# LEDCON_PCB.net
KiCad netlist of a schematic drawn in EAGLE
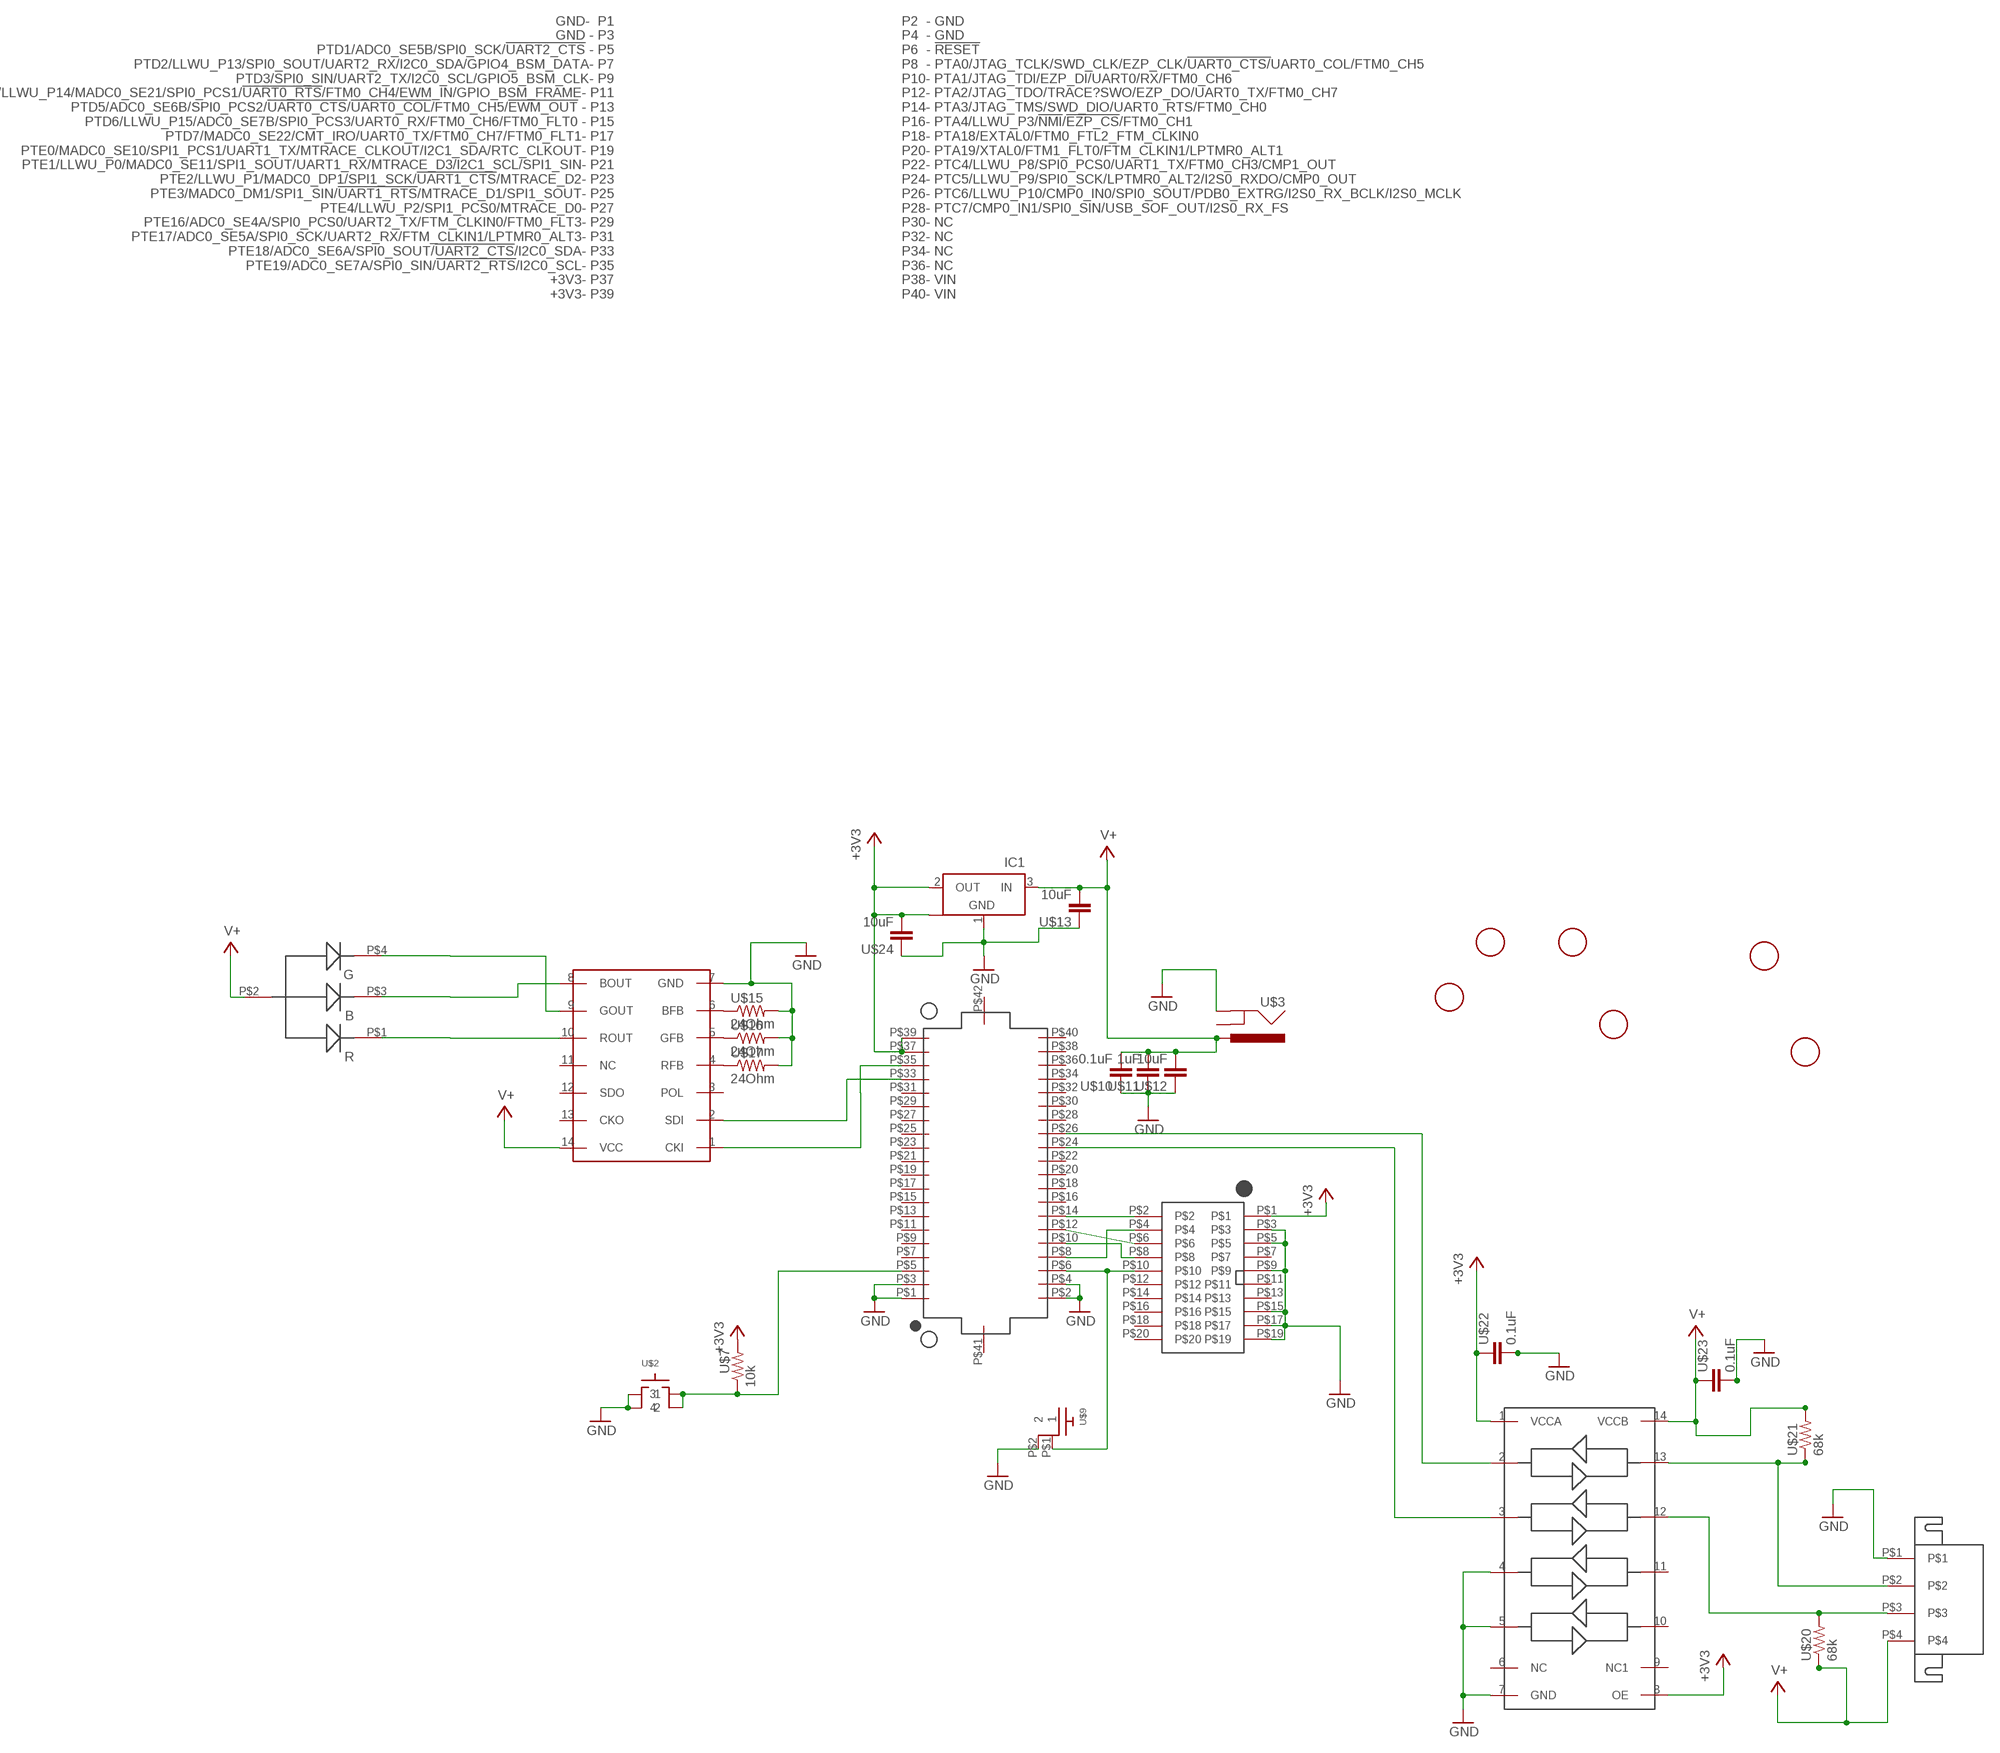
[diagram p0: schematic, sheet 1]

(export (version "E")
  (design (tool "Eeschema 10.0.6"))
  (components
    (comp (ref "IC1")
      (value "NCP1117ST33T3G_1")
      (footprint "eagle-import:SOT223")
      (fields (field (name "MFGN") "OnSemi") (field (name "MFGP") "NCP1117ST33T3G"))
      (libsource (lib "eagle-import") (part "NCP1117ST33T3G_1"))
    )
    (comp (ref "U$1")
      (value "MATE-N-LOK_643230-1")
      (footprint "eagle-import:MATE-N-LOK_643230-1")
      (fields (field (name "MFGN") "TE Connectivity") (field (name "MFGP") "643230-1"))
      (libsource (lib "eagle-import") (part "MATE-N-LOK_643230-1"))
    )
    (comp (ref "U$2")
      (value "SWITCH-TACTILE")
      (footprint "eagle-import:ESWITCH-TL3301PF")
      (libsource (lib "eagle-import") (part "SWITCH-TACTILE"))
    )
    (comp (ref "U$3")
      (value "BARREL_CUI_PJ-002A")
      (footprint "eagle-import:BARREL_CUI_PJ-002A")
      (libsource (lib "eagle-import") (part "BARREL_CUI_PJ-002A"))
    )
    (comp (ref "U$4")
      (value "DF12_F")
      (footprint "eagle-import:DF12_F")
      (fields (field (name "MFGN") "Hirose") (field (name "MFGP") "DF12(3.0)-40DP-0.5V(86)"))
      (libsource (lib "eagle-import") (part "DF12_F"))
    )
    (comp (ref "U$5")
      (value "RGLBED")
      (footprint "eagle-import:PLCC4_SMALL")
      (libsource (lib "eagle-import") (part "RGLBED"))
    )
    (comp (ref "U$6")
      (value "TXB0104")
      (footprint "eagle-import:PW_R-PDSO-G14")
      (fields (field (name "MFGN") "Texas Instruments"))
      (libsource (lib "eagle-import") (part "TXB0104"))
    )
    (comp (ref "U$7")
      (value "10k")
      (footprint "eagle-import:RF-C0805")
      (libsource (lib "eagle-import") (part "RF-R0805"))
    )
    (comp (ref "U$8")
      (value "WS2801")
      (footprint "eagle-import:SO14")
      (libsource (lib "eagle-import") (part "WS2801"))
    )
    (comp (ref "U$9")
      (value "RA_BUTTON")
      (footprint "eagle-import:RA_BUTTON")
      (libsource (lib "eagle-import") (part "RA_BUTTON"))
    )
    (comp (ref "U$10")
      (value "0.1uF")
      (footprint "eagle-import:C0805")
      (libsource (lib "eagle-import") (part "RF-C0805"))
    )
    (comp (ref "U$11")
      (value "1uF")
      (footprint "eagle-import:C0805")
      (libsource (lib "eagle-import") (part "RF-C0805"))
    )
    (comp (ref "U$12")
      (value "10uF")
      (footprint "eagle-import:C0805")
      (libsource (lib "eagle-import") (part "RF-C0805"))
    )
    (comp (ref "U$13")
      (value "10uF")
      (footprint "eagle-import:C0805")
      (libsource (lib "eagle-import") (part "RF-C0805"))
    )
    (comp (ref "U$14")
      (value "FIDUCIAL")
      (footprint "eagle-import:FIDUCIAL_1MM")
      (libsource (lib "eagle-import") (part "FIDUCIAL"))
    )
    (comp (ref "U$15")
      (value "24Ohm")
      (footprint "eagle-import:RF-C0805")
      (libsource (lib "eagle-import") (part "RF-R0805"))
    )
    (comp (ref "U$16")
      (value "24Ohm")
      (footprint "eagle-import:RF-C0805")
      (libsource (lib "eagle-import") (part "RF-R0805"))
    )
    (comp (ref "U$17")
      (value "24Ohm")
      (footprint "eagle-import:RF-C0805")
      (libsource (lib "eagle-import") (part "RF-R0805"))
    )
    (comp (ref "U$18")
      (value "FIDUCIAL")
      (footprint "eagle-import:FIDUCIAL_1MM")
      (libsource (lib "eagle-import") (part "FIDUCIAL"))
    )
    (comp (ref "U$19")
      (value "2X10JTAG")
      (footprint "eagle-import:2X10JTAG")
      (libsource (lib "eagle-import") (part "2X10JTAG"))
    )
    (comp (ref "U$20")
      (value "68k")
      (footprint "eagle-import:RF-C0805")
      (libsource (lib "eagle-import") (part "RF-R0805"))
    )
    (comp (ref "U$21")
      (value "68k")
      (footprint "eagle-import:RF-C0805")
      (libsource (lib "eagle-import") (part "RF-R0805"))
    )
    (comp (ref "U$22")
      (value "0.1uF")
      (footprint "eagle-import:C0805")
      (libsource (lib "eagle-import") (part "RF-C0805"))
    )
    (comp (ref "U$23")
      (value "0.1uF")
      (footprint "eagle-import:C0805")
      (libsource (lib "eagle-import") (part "RF-C0805"))
    )
    (comp (ref "U$24")
      (value "10uF")
      (footprint "eagle-import:C0805")
      (libsource (lib "eagle-import") (part "RF-C0805"))
    )
    (comp (ref "U$25")
      (value "FIDUCIAL")
      (footprint "eagle-import:FIDUCIAL_1MM")
      (libsource (lib "eagle-import") (part "FIDUCIAL"))
    )
    (comp (ref "U$26")
      (value "FIDUCIAL")
      (footprint "eagle-import:FIDUCIAL_1MM")
      (libsource (lib "eagle-import") (part "FIDUCIAL"))
    )
    (comp (ref "U$27")
      (value "FIDUCIAL")
      (footprint "eagle-import:FIDUCIAL_1MM")
      (libsource (lib "eagle-import") (part "FIDUCIAL"))
    )
    (comp (ref "U$28")
      (value "FIDUCIAL")
      (footprint "eagle-import:FIDUCIAL_1MM")
      (libsource (lib "eagle-import") (part "FIDUCIAL"))
    )
  )
  (nets
    (net (code "1") (name "+3V3") (class "Default")
      (node (ref "IC1") (pin "2") (pinfunction "OUT_2") (pintype "power_in"))
      (node (ref "IC1") (pin "4") (pinfunction "OUT1_4") (pintype "power_in"))
      (node (ref "U$19") (pin "P$1") (pinfunction "P$1_P$1") (pintype "bidirectional"))
      (node (ref "U$22") (pin "1") (pinfunction "1_1") (pintype "passive"))
      (node (ref "U$24") (pin "2") (pinfunction "2_2") (pintype "passive"))
      (node (ref "U$4") (pin "P$37") (pinfunction "+3V3_P$37") (pintype "bidirectional"))
      (node (ref "U$4") (pin "P$39") (pinfunction "+3V3_P$39") (pintype "bidirectional"))
      (node (ref "U$6") (pin "1") (pinfunction "VCCA_1") (pintype "bidirectional"))
      (node (ref "U$6") (pin "8") (pinfunction "OE_8") (pintype "bidirectional"))
      (node (ref "U$7") (pin "2") (pinfunction "2_2") (pintype "passive"))
    )
    (net (code "2") (name "GND") (class "Default")
      (node (ref "IC1") (pin "1") (pinfunction "GND_1") (pintype "power_in"))
      (node (ref "U$1") (pin "P$1") (pinfunction "P$1_P$1") (pintype "bidirectional"))
      (node (ref "U$10") (pin "1") (pinfunction "1_1") (pintype "passive"))
      (node (ref "U$11") (pin "1") (pinfunction "1_1") (pintype "passive"))
      (node (ref "U$12") (pin "1") (pinfunction "1_1") (pintype "passive"))
      (node (ref "U$13") (pin "1") (pinfunction "1_1") (pintype "passive"))
      (node (ref "U$15") (pin "2") (pinfunction "2_2") (pintype "passive"))
      (node (ref "U$16") (pin "2") (pinfunction "2_2") (pintype "passive"))
      (node (ref "U$17") (pin "2") (pinfunction "2_2") (pintype "passive"))
      (node (ref "U$19") (pin "P$15") (pinfunction "P$15_P$15") (pintype "bidirectional"))
      (node (ref "U$19") (pin "P$17") (pinfunction "P$17_P$17") (pintype "bidirectional"))
      (node (ref "U$19") (pin "P$19") (pinfunction "P$19_P$19") (pintype "bidirectional"))
      (node (ref "U$19") (pin "P$3") (pinfunction "P$3_P$3") (pintype "bidirectional"))
      (node (ref "U$19") (pin "P$5") (pinfunction "P$5_P$5") (pintype "bidirectional"))
      (node (ref "U$19") (pin "P$9") (pinfunction "P$9_P$9") (pintype "bidirectional"))
      (node (ref "U$2") (pin "1") (pinfunction "1_1") (pintype "input"))
      (node (ref "U$2") (pin "2") (pinfunction "2_2") (pintype "input"))
      (node (ref "U$22") (pin "2") (pinfunction "2_2") (pintype "passive"))
      (node (ref "U$23") (pin "2") (pinfunction "2_2") (pintype "passive"))
      (node (ref "U$24") (pin "1") (pinfunction "1_1") (pintype "passive"))
      (node (ref "U$3") (pin "P$2") (pinfunction "GND_P$2") (pintype "bidirectional"))
      (node (ref "U$4") (pin "P$1") (pinfunction "GND_P$1") (pintype "bidirectional"))
      (node (ref "U$4") (pin "P$2") (pinfunction "GND_P$2") (pintype "bidirectional"))
      (node (ref "U$4") (pin "P$3") (pinfunction "GND_P$3") (pintype "bidirectional"))
      (node (ref "U$4") (pin "P$4") (pinfunction "GND_P$4") (pintype "bidirectional"))
      (node (ref "U$6") (pin "4") (pinfunction "P$4_4") (pintype "bidirectional"))
      (node (ref "U$6") (pin "5") (pinfunction "P$5_5") (pintype "bidirectional"))
      (node (ref "U$6") (pin "7") (pinfunction "GND_7") (pintype "bidirectional"))
      (node (ref "U$8") (pin "7") (pinfunction "GND_7") (pintype "bidirectional"))
      (node (ref "U$9") (pin "P$2") (pinfunction "2_P$2") (pintype "input"))
    )
    (net (code "3") (name "Net-(U$4-PTA0{slash}JTAG_TCLK{slash}SWD_CLK{slash}EZP_CLK{slash}~{UART0_CTS{slash}}UART0_COL{slash}FTM0_CH5)") (class "Default")
      (node (ref "U$19") (pin "P$4") (pinfunction "P$4_P$4") (pintype "bidirectional"))
      (node (ref "U$4") (pin "P$8") (pinfunction "PTA0/JTAG_TCLK/SWD_CLK/EZP_CLK/~{UART0_CTS/}UART0_COL/FTM0_CH5_P$8") (pintype "bidirectional"))
    )
    (net (code "4") (name "Net-(U$4-PTA1{slash}JTAG_TDI{slash}EZP_DI{slash}UART0{slash}RX{slash}FTM0_CH6)") (class "Default")
      (node (ref "U$19") (pin "P$8") (pinfunction "P$8_P$8") (pintype "bidirectional"))
      (node (ref "U$4") (pin "P$10") (pinfunction "PTA1/JTAG_TDI/EZP_DI/UART0/RX/FTM0_CH6_P$10") (pintype "bidirectional"))
    )
    (net (code "5") (name "Net-(U$4-PTA2{slash}JTAG_TDO{slash}TRACE?SWO{slash}EZP_DO{slash}UART0_TX{slash}FTM0_CH7)") (class "Default")
      (node (ref "U$19") (pin "P$6") (pinfunction "P$6_P$6") (pintype "bidirectional"))
      (node (ref "U$4") (pin "P$12") (pinfunction "PTA2/JTAG_TDO/TRACE?SWO/EZP_DO/UART0_TX/FTM0_CH7_P$12") (pintype "bidirectional"))
    )
    (net (code "6") (name "Net-(U$4-PTA3{slash}JTAG_TMS{slash}SWD_DIO{slash}UART0_RTS{slash}FTM0_CH0)") (class "Default")
      (node (ref "U$19") (pin "P$2") (pinfunction "P$2_P$2") (pintype "bidirectional"))
      (node (ref "U$4") (pin "P$14") (pinfunction "PTA3/JTAG_TMS/SWD_DIO/UART0_RTS/FTM0_CH0_P$14") (pintype "bidirectional"))
    )
    (net (code "7") (name "Net-(U$4-PTC5{slash}LLWU_P8{slash}SPI0_PCS0{slash}UART1_TX{slash}FTM0_CH3{slash}CMP1_OUT)") (class "Default")
      (node (ref "U$4") (pin "P$24") (pinfunction "PTC5/LLWU_P8/SPI0_PCS0/UART1_TX/FTM0_CH3/CMP1_OUT_P$24") (pintype "bidirectional"))
      (node (ref "U$6") (pin "3") (pinfunction "P$3_3") (pintype "bidirectional"))
    )
    (net (code "8") (name "Net-(U$4-PTC6{slash}LLWU_P10{slash}CMP0_IN0{slash}SPI0_SOUT{slash}PDB0_EXTRG{slash}I2S0_RX_BCLK{slash}I2S0_MCLK)") (class "Default")
      (node (ref "U$4") (pin "P$26") (pinfunction "PTC6/LLWU_P10/CMP0_IN0/SPI0_SOUT/PDB0_EXTRG/I2S0_RX_BCLK/I2S0_MCLK_P$26") (pintype "bidirectional"))
      (node (ref "U$6") (pin "2") (pinfunction "P$2_2") (pintype "bidirectional"))
    )
    (net (code "9") (name "Net-(U$4-PTD1{slash}ADC0_SE5B{slash}SPI0_SCK{slash}~{UART2_CTS})") (class "Default")
      (node (ref "U$2") (pin "3") (pinfunction "3_3") (pintype "input"))
      (node (ref "U$2") (pin "4") (pinfunction "4_4") (pintype "input"))
      (node (ref "U$4") (pin "P$5") (pinfunction "PTD1/ADC0_SE5B/SPI0_SCK/~{UART2_CTS}_P$5") (pintype "bidirectional"))
      (node (ref "U$7") (pin "1") (pinfunction "1_1") (pintype "passive"))
    )
    (net (code "10") (name "Net-(U$4-PTE18{slash}ADC0_SE6A{slash}SPI0_SOUT{slash}~{UART2_CTS}{slash}I2C0_SDA)") (class "Default")
      (node (ref "U$4") (pin "P$33") (pinfunction "PTE18/ADC0_SE6A/SPI0_SOUT/~{UART2_CTS}/I2C0_SDA_P$33") (pintype "bidirectional"))
      (node (ref "U$8") (pin "2") (pinfunction "SDI_2") (pintype "bidirectional"))
    )
    (net (code "11") (name "Net-(U$4-PTE19{slash}ADC0_SE7A{slash}SPI0_SIN{slash}~{UART2_RTS}{slash}I2C0_SCL)") (class "Default")
      (node (ref "U$4") (pin "P$35") (pinfunction "PTE19/ADC0_SE7A/SPI0_SIN/~{UART2_RTS}/I2C0_SCL_P$35") (pintype "bidirectional"))
      (node (ref "U$8") (pin "1") (pinfunction "CKI_1") (pintype "bidirectional"))
    )
    (net (code "12") (name "Net-(U$4-~{RESET})") (class "Default")
      (node (ref "U$19") (pin "P$10") (pinfunction "P$10_P$10") (pintype "bidirectional"))
      (node (ref "U$4") (pin "P$6") (pinfunction "~{RESET}_P$6") (pintype "bidirectional"))
      (node (ref "U$9") (pin "P$1") (pinfunction "1_P$1") (pintype "input"))
    )
    (net (code "13") (name "Net-(U$5-BLUE)") (class "Default")
      (node (ref "U$5") (pin "P$3") (pinfunction "BLUE_P$3") (pintype "bidirectional"))
      (node (ref "U$8") (pin "8") (pinfunction "BOUT_8") (pintype "bidirectional"))
    )
    (net (code "14") (name "Net-(U$5-GREEN)") (class "Default")
      (node (ref "U$5") (pin "P$4") (pinfunction "GREEN_P$4") (pintype "bidirectional"))
      (node (ref "U$8") (pin "9") (pinfunction "GOUT_9") (pintype "bidirectional"))
    )
    (net (code "15") (name "Net-(U$5-RED)") (class "Default")
      (node (ref "U$5") (pin "P$1") (pinfunction "RED_P$1") (pintype "bidirectional"))
      (node (ref "U$8") (pin "10") (pinfunction "ROUT_10") (pintype "bidirectional"))
    )
    (net (code "16") (name "Net-(U$6-P$12)") (class "Default")
      (node (ref "U$1") (pin "P$3") (pinfunction "P$3_P$3") (pintype "bidirectional"))
      (node (ref "U$20") (pin "2") (pinfunction "2_2") (pintype "passive"))
      (node (ref "U$6") (pin "12") (pinfunction "P$12_12") (pintype "bidirectional"))
    )
    (net (code "17") (name "Net-(U$6-P$13)") (class "Default")
      (node (ref "U$1") (pin "P$2") (pinfunction "P$2_P$2") (pintype "bidirectional"))
      (node (ref "U$21") (pin "1") (pinfunction "1_1") (pintype "passive"))
      (node (ref "U$6") (pin "13") (pinfunction "P$13_13") (pintype "bidirectional"))
    )
    (net (code "18") (name "Net-(U$8-BFB)") (class "Default")
      (node (ref "U$15") (pin "1") (pinfunction "1_1") (pintype "passive"))
      (node (ref "U$8") (pin "6") (pinfunction "BFB_6") (pintype "bidirectional"))
    )
    (net (code "19") (name "Net-(U$8-GFB)") (class "Default")
      (node (ref "U$16") (pin "1") (pinfunction "1_1") (pintype "passive"))
      (node (ref "U$8") (pin "5") (pinfunction "GFB_5") (pintype "bidirectional"))
    )
    (net (code "20") (name "Net-(U$8-RFB)") (class "Default")
      (node (ref "U$17") (pin "1") (pinfunction "1_1") (pintype "passive"))
      (node (ref "U$8") (pin "4") (pinfunction "RFB_4") (pintype "bidirectional"))
    )
    (net (code "21") (name "V+") (class "Default")
      (node (ref "IC1") (pin "3") (pinfunction "IN_3") (pintype "input"))
      (node (ref "U$1") (pin "P$4") (pinfunction "P$4_P$4") (pintype "bidirectional"))
      (node (ref "U$10") (pin "2") (pinfunction "2_2") (pintype "passive"))
      (node (ref "U$11") (pin "2") (pinfunction "2_2") (pintype "passive"))
      (node (ref "U$12") (pin "2") (pinfunction "2_2") (pintype "passive"))
      (node (ref "U$13") (pin "2") (pinfunction "2_2") (pintype "passive"))
      (node (ref "U$20") (pin "1") (pinfunction "1_1") (pintype "passive"))
      (node (ref "U$21") (pin "2") (pinfunction "2_2") (pintype "passive"))
      (node (ref "U$23") (pin "1") (pinfunction "1_1") (pintype "passive"))
      (node (ref "U$3") (pin "P$1") (pinfunction "PWR_P$1") (pintype "bidirectional"))
      (node (ref "U$5") (pin "P$2") (pinfunction "ANODE_P$2") (pintype "bidirectional"))
      (node (ref "U$6") (pin "14") (pinfunction "VCCB_14") (pintype "bidirectional"))
      (node (ref "U$8") (pin "14") (pinfunction "VCC_14") (pintype "bidirectional"))
    )
    (net (code "22") (name "unconnected-(U$3-GNDBREAK-PadP$3)") (class "Default")
      (node (ref "U$3") (pin "P$3") (pinfunction "GNDBREAK_P$3") (pintype "bidirectional"))
    )
    (net (code "23") (name "unconnected-(U$4-NC-PadP$30)") (class "Default")
      (node (ref "U$4") (pin "P$30") (pinfunction "NC_P$30") (pintype "bidirectional"))
    )
    (net (code "24") (name "unconnected-(U$4-NC-PadP$32)") (class "Default")
      (node (ref "U$4") (pin "P$32") (pinfunction "NC_P$32") (pintype "bidirectional"))
    )
    (net (code "25") (name "unconnected-(U$4-NC-PadP$34)") (class "Default")
      (node (ref "U$4") (pin "P$34") (pinfunction "NC_P$34") (pintype "bidirectional"))
    )
    (net (code "26") (name "unconnected-(U$4-NC-PadP$36)") (class "Default")
      (node (ref "U$4") (pin "P$36") (pinfunction "NC_P$36") (pintype "bidirectional"))
    )
    (net (code "27") (name "unconnected-(U$4-PTA4{slash}LLWU_P3{slash}~{NMI}{slash}~{EZP_CS}{slash}FTM0_CH1-PadP$16)") (class "Default")
      (node (ref "U$4") (pin "P$16") (pinfunction "PTA4/LLWU_P3/~{NMI}/~{EZP_CS}/FTM0_CH1_P$16") (pintype "bidirectional"))
    )
    (net (code "28") (name "unconnected-(U$4-PTA18{slash}EXTAL0{slash}FTM0_FTL2_FTM_CLKIN0-PadP$18)") (class "Default")
      (node (ref "U$4") (pin "P$18") (pinfunction "PTA18/EXTAL0/FTM0_FTL2_FTM_CLKIN0_P$18") (pintype "bidirectional"))
    )
    (net (code "29") (name "unconnected-(U$4-PTA19{slash}XTAL0{slash}FTM1_FLT0{slash}FTM_CLKIN1{slash}LPTMR0_ALT1-PadP$20)") (class "Default")
      (node (ref "U$4") (pin "P$20") (pinfunction "PTA19/XTAL0/FTM1_FLT0/FTM_CLKIN1/LPTMR0_ALT1_P$20") (pintype "bidirectional"))
    )
    (net (code "30") (name "unconnected-(U$4-PTC4{slash}LLWU_P8{slash}SPI0_PCS0{slash}UART1_TX{slash}FTM0_CH3{slash}CMP1_OUT-PadP$22)") (class "Default")
      (node (ref "U$4") (pin "P$22") (pinfunction "PTC4/LLWU_P8/SPI0_PCS0/UART1_TX/FTM0_CH3/CMP1_OUT_P$22") (pintype "bidirectional"))
    )
    (net (code "31") (name "unconnected-(U$4-PTC7{slash}CMP0_IN1{slash}SPI0_SIN{slash}USB_SOF_OUT{slash}I2S0_RX_FS-PadP$28)") (class "Default")
      (node (ref "U$4") (pin "P$28") (pinfunction "PTC7/CMP0_IN1/SPI0_SIN/USB_SOF_OUT/I2S0_RX_FS_P$28") (pintype "bidirectional"))
    )
    (net (code "32") (name "unconnected-(U$4-PTD2{slash}LLWU_P13{slash}SPI0_SOUT{slash}UART2_RX{slash}I2C0_SDA{slash}GPIO4_BSM_DATA-PadP$7)") (class "Default")
      (node (ref "U$4") (pin "P$7") (pinfunction "PTD2/LLWU_P13/SPI0_SOUT/UART2_RX/I2C0_SDA/GPIO4_BSM_DATA_P$7") (pintype "bidirectional"))
    )
    (net (code "33") (name "unconnected-(U$4-PTD3{slash}SPI0_SIN{slash}UART2_TX{slash}I2C0_SCL{slash}GPIO5_BSM_CLK-PadP$9)") (class "Default")
      (node (ref "U$4") (pin "P$9") (pinfunction "PTD3/SPI0_SIN/UART2_TX/I2C0_SCL/GPIO5_BSM_CLK_P$9") (pintype "bidirectional"))
    )
    (net (code "34") (name "unconnected-(U$4-PTD4{slash}LLWU_P14{slash}MADC0_SE21{slash}SPI0_PCS1{slash}~{UART0_RTS}{slash}FTM0_CH4{slash}EWM_IN{slash}GPIO_BSM_FRAME-PadP$11)") (class "Default")
      (node (ref "U$4") (pin "P$11") (pinfunction "PTD4/LLWU_P14/MADC0_SE21/SPI0_PCS1/~{UART0_RTS}/FTM0_CH4/EWM_IN/GPIO_BSM_FRAME_P$11") (pintype "bidirectional"))
    )
    (net (code "35") (name "unconnected-(U$4-PTD5{slash}ADC0_SE6B{slash}SPI0_PCS2{slash}~{UART0_CTS}{slash}~{UART0_COL}{slash}FTM0_CH5{slash}~{EWM_OUT}-PadP$13)") (class "Default")
      (node (ref "U$4") (pin "P$13") (pinfunction "PTD5/ADC0_SE6B/SPI0_PCS2/~{UART0_CTS}/~{UART0_COL}/FTM0_CH5/~{EWM_OUT}_P$13") (pintype "bidirectional"))
    )
    (net (code "36") (name "unconnected-(U$4-PTD6{slash}LLWU_P15{slash}ADC0_SE7B{slash}SPI0_PCS3{slash}UART0_RX{slash}FTM0_CH6{slash}FTM0_FLT0-PadP$15)") (class "Default")
      (node (ref "U$4") (pin "P$15") (pinfunction "PTD6/LLWU_P15/ADC0_SE7B/SPI0_PCS3/UART0_RX/FTM0_CH6/FTM0_FLT0_P$15") (pintype "bidirectional"))
    )
    (net (code "37") (name "unconnected-(U$4-PTD7{slash}MADC0_SE22{slash}CMT_IRO{slash}UART0_TX{slash}FTM0_CH7{slash}FTM0_FLT1-PadP$17)") (class "Default")
      (node (ref "U$4") (pin "P$17") (pinfunction "PTD7/MADC0_SE22/CMT_IRO/UART0_TX/FTM0_CH7/FTM0_FLT1_P$17") (pintype "bidirectional"))
    )
    (net (code "38") (name "unconnected-(U$4-PTE0{slash}MADC0_SE10{slash}SPI1_PCS1{slash}UART1_TX{slash}MTRACE_CLKOUT{slash}I2C1_SDA{slash}RTC_CLKOUT-PadP$19)") (class "Default")
      (node (ref "U$4") (pin "P$19") (pinfunction "PTE0/MADC0_SE10/SPI1_PCS1/UART1_TX/MTRACE_CLKOUT/I2C1_SDA/RTC_CLKOUT_P$19") (pintype "bidirectional"))
    )
    (net (code "39") (name "unconnected-(U$4-PTE1{slash}LLWU_P0{slash}MADC0_SE11{slash}SPI1_SOUT{slash}UART1_RX{slash}MTRACE_D3{slash}I2C1_SCL{slash}SPI1_SIN-PadP$21)") (class "Default")
      (node (ref "U$4") (pin "P$21") (pinfunction "PTE1/LLWU_P0/MADC0_SE11/SPI1_SOUT/UART1_RX/MTRACE_D3/I2C1_SCL/SPI1_SIN_P$21") (pintype "bidirectional"))
    )
    (net (code "40") (name "unconnected-(U$4-PTE2{slash}LLWU_P1{slash}MADC0_DP1{slash}SPI1_SCK{slash}~{UART1_CTS}{slash}MTRACE_D2-PadP$23)") (class "Default")
      (node (ref "U$4") (pin "P$23") (pinfunction "PTE2/LLWU_P1/MADC0_DP1/SPI1_SCK/~{UART1_CTS}/MTRACE_D2_P$23") (pintype "bidirectional"))
    )
    (net (code "41") (name "unconnected-(U$4-PTE3{slash}MADC0_DM1{slash}SPI1_SIN{slash}~{UART1_RTS}{slash}MTRACE_D1{slash}SPI1_SOUT-PadP$25)") (class "Default")
      (node (ref "U$4") (pin "P$25") (pinfunction "PTE3/MADC0_DM1/SPI1_SIN/~{UART1_RTS}/MTRACE_D1/SPI1_SOUT_P$25") (pintype "bidirectional"))
    )
    (net (code "42") (name "unconnected-(U$4-PTE4{slash}LLWU_P2{slash}SPI1_PCS0{slash}MTRACE_D0-PadP$27)") (class "Default")
      (node (ref "U$4") (pin "P$27") (pinfunction "PTE4/LLWU_P2/SPI1_PCS0/MTRACE_D0_P$27") (pintype "bidirectional"))
    )
    (net (code "43") (name "unconnected-(U$4-PTE16{slash}ADC0_SE4A{slash}SPI0_PCS0{slash}UART2_TX{slash}FTM_CLKIN0{slash}FTM0_FLT3-PadP$29)") (class "Default")
      (node (ref "U$4") (pin "P$29") (pinfunction "PTE16/ADC0_SE4A/SPI0_PCS0/UART2_TX/FTM_CLKIN0/FTM0_FLT3_P$29") (pintype "bidirectional"))
    )
    (net (code "44") (name "unconnected-(U$4-PTE17{slash}ADC0_SE5A{slash}SPI0_SCK{slash}UART2_RX{slash}FTM_CLKIN1{slash}LPTMR0_ALT3-PadP$31)") (class "Default")
      (node (ref "U$4") (pin "P$31") (pinfunction "PTE17/ADC0_SE5A/SPI0_SCK/UART2_RX/FTM_CLKIN1/LPTMR0_ALT3_P$31") (pintype "bidirectional"))
    )
    (net (code "45") (name "unconnected-(U$4-PadP$41)") (class "Default")
      (node (ref "U$4") (pin "P$41") (pinfunction "P$41_P$41") (pintype "bidirectional"))
    )
    (net (code "46") (name "unconnected-(U$4-PadP$42)") (class "Default")
      (node (ref "U$4") (pin "P$42") (pinfunction "P$42_P$42") (pintype "bidirectional"))
    )
    (net (code "47") (name "unconnected-(U$4-VIN-PadP$38)") (class "Default")
      (node (ref "U$4") (pin "P$38") (pinfunction "VIN_P$38") (pintype "bidirectional"))
    )
    (net (code "48") (name "unconnected-(U$4-VIN-PadP$40)") (class "Default")
      (node (ref "U$4") (pin "P$40") (pinfunction "VIN_P$40") (pintype "bidirectional"))
    )
    (net (code "49") (name "unconnected-(U$6-NC-Pad6)") (class "Default")
      (node (ref "U$6") (pin "6") (pinfunction "NC_6") (pintype "bidirectional"))
    )
    (net (code "50") (name "unconnected-(U$6-NC1-Pad9)") (class "Default")
      (node (ref "U$6") (pin "9") (pinfunction "NC1_9") (pintype "bidirectional"))
    )
    (net (code "51") (name "unconnected-(U$6-P$10-Pad10)") (class "Default")
      (node (ref "U$6") (pin "10") (pinfunction "P$10_10") (pintype "bidirectional"))
    )
    (net (code "52") (name "unconnected-(U$6-P$11-Pad11)") (class "Default")
      (node (ref "U$6") (pin "11") (pinfunction "P$11_11") (pintype "bidirectional"))
    )
    (net (code "53") (name "unconnected-(U$8-CKO-Pad13)") (class "Default")
      (node (ref "U$8") (pin "13") (pinfunction "CKO_13") (pintype "bidirectional"))
    )
    (net (code "54") (name "unconnected-(U$8-NC-Pad11)") (class "Default")
      (node (ref "U$8") (pin "11") (pinfunction "NC_11") (pintype "bidirectional"))
    )
    (net (code "55") (name "unconnected-(U$8-POL-Pad3)") (class "Default")
      (node (ref "U$8") (pin "3") (pinfunction "POL_3") (pintype "bidirectional"))
    )
    (net (code "56") (name "unconnected-(U$8-SDO-Pad12)") (class "Default")
      (node (ref "U$8") (pin "12") (pinfunction "SDO_12") (pintype "bidirectional"))
    )
    (net (code "57") (name "unconnected-(U$19-PadP$7)") (class "Default")
      (node (ref "U$19") (pin "P$7") (pinfunction "P$7_P$7") (pintype "bidirectional"))
    )
    (net (code "58") (name "unconnected-(U$19-PadP$11)") (class "Default")
      (node (ref "U$19") (pin "P$11") (pinfunction "P$11_P$11") (pintype "bidirectional"))
    )
    (net (code "59") (name "unconnected-(U$19-PadP$12)") (class "Default")
      (node (ref "U$19") (pin "P$12") (pinfunction "P$12_P$12") (pintype "bidirectional"))
    )
    (net (code "60") (name "unconnected-(U$19-PadP$13)") (class "Default")
      (node (ref "U$19") (pin "P$13") (pinfunction "P$13_P$13") (pintype "bidirectional"))
    )
    (net (code "61") (name "unconnected-(U$19-PadP$14)") (class "Default")
      (node (ref "U$19") (pin "P$14") (pinfunction "P$14_P$14") (pintype "bidirectional"))
    )
    (net (code "62") (name "unconnected-(U$19-PadP$16)") (class "Default")
      (node (ref "U$19") (pin "P$16") (pinfunction "P$16_P$16") (pintype "bidirectional"))
    )
    (net (code "63") (name "unconnected-(U$19-PadP$18)") (class "Default")
      (node (ref "U$19") (pin "P$18") (pinfunction "P$18_P$18") (pintype "bidirectional"))
    )
    (net (code "64") (name "unconnected-(U$19-PadP$20)") (class "Default")
      (node (ref "U$19") (pin "P$20") (pinfunction "P$20_P$20") (pintype "bidirectional"))
    )
  )
)
